# hall_test_v5.net
KiCad netlist of a schematic drawn in EAGLE
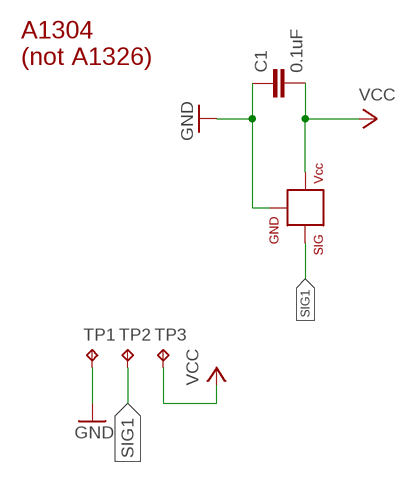
[diagram p0: schematic, sheet 1]

(export (version "E")
  (design (tool "Eeschema 10.0.6"))
  (components
    (comp (ref "C1")
      (value "0.1uF")
      (footprint "eagle-import:0603-CAP")
      (libsource (lib "eagle-import") (part "CAP0603-CAP"))
    )
    (comp (ref "HALL")
      (value "HALLEFFECT-A1326")
      (footprint "eagle-import:SOT23-3")
      (libsource (lib "eagle-import") (part "HALLEFFECT-A1326"))
    )
    (comp (ref "TP1")
      (value "TPTP10SQ")
      (footprint "eagle-import:TP10SQ")
      (libsource (lib "eagle-import") (part "TPTP10SQ"))
    )
    (comp (ref "TP2")
      (value "TPTP10SQ")
      (footprint "eagle-import:TP10SQ")
      (libsource (lib "eagle-import") (part "TPTP10SQ"))
    )
    (comp (ref "TP3")
      (value "TPTP10SQ")
      (footprint "eagle-import:TP10SQ")
      (libsource (lib "eagle-import") (part "TPTP10SQ"))
    )
  )
  (nets
    (net (code "1") (name "GND") (class "Default")
      (node (ref "C1") (pin "1") (pinfunction "1_1") (pintype "passive"))
      (node (ref "HALL") (pin "3") (pinfunction "GND_3") (pintype "bidirectional"))
      (node (ref "TP1") (pin "TP") (pinfunction "TP_TP") (pintype "input"))
    )
    (net (code "2") (name "SIG1") (class "Default")
      (node (ref "HALL") (pin "2") (pinfunction "SIG_2") (pintype "bidirectional"))
      (node (ref "TP2") (pin "TP") (pinfunction "TP_TP") (pintype "input"))
    )
    (net (code "3") (name "VCC") (class "Default")
      (node (ref "C1") (pin "2") (pinfunction "2_2") (pintype "passive"))
      (node (ref "HALL") (pin "1") (pinfunction "VCC_1") (pintype "bidirectional"))
      (node (ref "TP3") (pin "TP") (pinfunction "TP_TP") (pintype "input"))
    )
  )
)
